# STX3.net
KiCad netlist of a schematic drawn in EAGLE
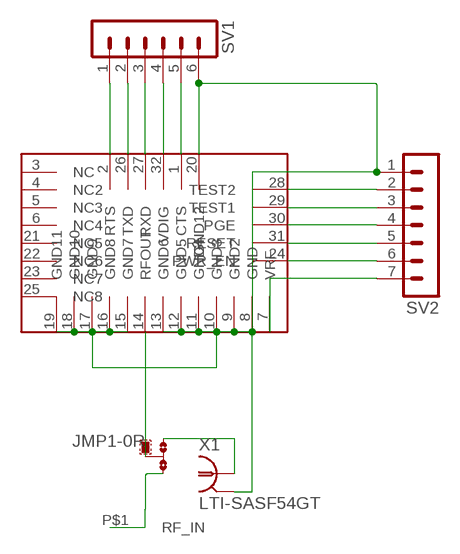
[diagram p0: schematic, sheet 1]

(export (version "E")
  (design (tool "Eeschema 10.0.6"))
  (components
    (comp (ref "JMP1")
      (value "0R-JUMPC")
      (footprint "eagle-import:C0R-JMP")
      (libsource (lib "eagle-import") (part "0R-JUMPC"))
    )
    (comp (ref "SV1")
      (value "MA06-1")
      (footprint "eagle-import:MA06-1")
      (libsource (lib "eagle-import") (part "MA06-1"))
    )
    (comp (ref "SV2")
      (value "MA07-1")
      (footprint "eagle-import:MA07-1")
      (libsource (lib "eagle-import") (part "MA07-1"))
    )
    (comp (ref "U$1")
      (value "STX3")
      (footprint "eagle-import:STX3")
      (libsource (lib "eagle-import") (part "STX3"))
    )
    (comp (ref "U$2")
      (value "GSANTENNA")
      (footprint "eagle-import:GSANTENNA")
      (libsource (lib "eagle-import") (part "GSANTENNA"))
    )
    (comp (ref "X1")
      (value "LTI-SASF54GT")
      (footprint "eagle-import:LTI-SASF54GT")
      (libsource (lib "eagle-import") (part "LTI-SASF54GT"))
    )
  )
  (nets
    (net (code "1") (name "Net-(JMP1-Pad1)") (class "Default")
      (node (ref "JMP1") (pin "1") (pinfunction "1_1") (pintype "passive"))
      (node (ref "X1") (pin "1") (pinfunction "1_1") (pintype "passive"))
    )
    (net (code "2") (name "Net-(U$1-CTS)") (class "Default")
      (node (ref "SV1") (pin "5") (pinfunction "5_5") (pintype "passive"))
      (node (ref "U$1") (pin "1") (pinfunction "CTS_1") (pintype "bidirectional"))
    )
    (net (code "3") (name "Net-(U$1-GND)") (class "Default")
      (node (ref "SV1") (pin "6") (pinfunction "6_6") (pintype "passive"))
      (node (ref "SV2") (pin "1") (pinfunction "1_1") (pintype "passive"))
      (node (ref "U$1") (pin "10") (pinfunction "GND3_10") (pintype "bidirectional"))
      (node (ref "U$1") (pin "11") (pinfunction "GND4_11") (pintype "bidirectional"))
      (node (ref "U$1") (pin "12") (pinfunction "GND5_12") (pintype "bidirectional"))
      (node (ref "U$1") (pin "13") (pinfunction "GND6_13") (pintype "bidirectional"))
      (node (ref "U$1") (pin "15") (pinfunction "GND7_15") (pintype "bidirectional"))
      (node (ref "U$1") (pin "16") (pinfunction "GND8_16") (pintype "bidirectional"))
      (node (ref "U$1") (pin "17") (pinfunction "GND9_17") (pintype "bidirectional"))
      (node (ref "U$1") (pin "18") (pinfunction "GND10_18") (pintype "bidirectional"))
      (node (ref "U$1") (pin "19") (pinfunction "GND11_19") (pintype "bidirectional"))
      (node (ref "U$1") (pin "20") (pinfunction "GND12_20") (pintype "bidirectional"))
      (node (ref "U$1") (pin "8") (pinfunction "GND_8") (pintype "bidirectional"))
      (node (ref "U$1") (pin "9") (pinfunction "GND2_9") (pintype "bidirectional"))
      (node (ref "X1") (pin "2") (pinfunction "2_2") (pintype "passive"))
      (node (ref "X1") (pin "3") (pinfunction "2_3") (pintype "passive"))
      (node (ref "X1") (pin "4") (pinfunction "2_4") (pintype "passive"))
      (node (ref "X1") (pin "5") (pinfunction "2_5") (pintype "passive"))
    )
    (net (code "4") (name "Net-(U$1-PGE)") (class "Default")
      (node (ref "SV2") (pin "4") (pinfunction "4_4") (pintype "passive"))
      (node (ref "U$1") (pin "30") (pinfunction "PGE_30") (pintype "bidirectional"))
    )
    (net (code "5") (name "Net-(U$1-PWR_EN)") (class "Default")
      (node (ref "SV2") (pin "6") (pinfunction "6_6") (pintype "passive"))
      (node (ref "U$1") (pin "24") (pinfunction "PWR_EN_24") (pintype "bidirectional"))
    )
    (net (code "6") (name "Net-(U$1-RESET)") (class "Default")
      (node (ref "SV2") (pin "5") (pinfunction "5_5") (pintype "passive"))
      (node (ref "U$1") (pin "31") (pinfunction "RESET_31") (pintype "bidirectional"))
    )
    (net (code "7") (name "Net-(U$1-RFOUT)") (class "Default")
      (node (ref "JMP1") (pin "2") (pinfunction "2_2") (pintype "passive"))
      (node (ref "U$1") (pin "14") (pinfunction "RFOUT_14") (pintype "bidirectional"))
    )
    (net (code "8") (name "Net-(U$1-RTS)") (class "Default")
      (node (ref "SV1") (pin "1") (pinfunction "1_1") (pintype "passive"))
      (node (ref "U$1") (pin "2") (pinfunction "RTS_2") (pintype "bidirectional"))
    )
    (net (code "9") (name "Net-(U$1-RXD)") (class "Default")
      (node (ref "SV1") (pin "3") (pinfunction "3_3") (pintype "passive"))
      (node (ref "U$1") (pin "27") (pinfunction "RXD_27") (pintype "bidirectional"))
    )
    (net (code "10") (name "Net-(U$1-TEST1)") (class "Default")
      (node (ref "SV2") (pin "3") (pinfunction "3_3") (pintype "passive"))
      (node (ref "U$1") (pin "29") (pinfunction "TEST1_29") (pintype "bidirectional"))
    )
    (net (code "11") (name "Net-(U$1-TEST2)") (class "Default")
      (node (ref "SV2") (pin "2") (pinfunction "2_2") (pintype "passive"))
      (node (ref "U$1") (pin "28") (pinfunction "TEST2_28") (pintype "bidirectional"))
    )
    (net (code "12") (name "Net-(U$1-TXD)") (class "Default")
      (node (ref "SV1") (pin "2") (pinfunction "2_2") (pintype "passive"))
      (node (ref "U$1") (pin "26") (pinfunction "TXD_26") (pintype "bidirectional"))
    )
    (net (code "13") (name "Net-(U$1-VDIG)") (class "Default")
      (node (ref "SV1") (pin "4") (pinfunction "4_4") (pintype "passive"))
      (node (ref "U$1") (pin "32") (pinfunction "VDIG_32") (pintype "bidirectional"))
    )
    (net (code "14") (name "Net-(U$1-VRF)") (class "Default")
      (node (ref "SV2") (pin "7") (pinfunction "7_7") (pintype "passive"))
      (node (ref "U$1") (pin "7") (pinfunction "VRF_7") (pintype "bidirectional"))
    )
    (net (code "15") (name "Net-(U$2-RF_IN)") (class "Default")
      (node (ref "JMP1") (pin "3") (pinfunction "3_3") (pintype "passive"))
      (node (ref "U$2") (pin "P$1") (pinfunction "RF_IN_P$1") (pintype "bidirectional"))
    )
    (net (code "16") (name "unconnected-(U$1-NC-Pad3)") (class "Default")
      (node (ref "U$1") (pin "3") (pinfunction "NC_3") (pintype "bidirectional"))
    )
    (net (code "17") (name "unconnected-(U$1-NC2-Pad4)") (class "Default")
      (node (ref "U$1") (pin "4") (pinfunction "NC2_4") (pintype "bidirectional"))
    )
    (net (code "18") (name "unconnected-(U$1-NC3-Pad5)") (class "Default")
      (node (ref "U$1") (pin "5") (pinfunction "NC3_5") (pintype "bidirectional"))
    )
    (net (code "19") (name "unconnected-(U$1-NC4-Pad6)") (class "Default")
      (node (ref "U$1") (pin "6") (pinfunction "NC4_6") (pintype "bidirectional"))
    )
    (net (code "20") (name "unconnected-(U$1-NC5-Pad21)") (class "Default")
      (node (ref "U$1") (pin "21") (pinfunction "NC5_21") (pintype "bidirectional"))
    )
    (net (code "21") (name "unconnected-(U$1-NC6-Pad22)") (class "Default")
      (node (ref "U$1") (pin "22") (pinfunction "NC6_22") (pintype "bidirectional"))
    )
    (net (code "22") (name "unconnected-(U$1-NC7-Pad23)") (class "Default")
      (node (ref "U$1") (pin "23") (pinfunction "NC7_23") (pintype "bidirectional"))
    )
    (net (code "23") (name "unconnected-(U$1-NC8-Pad25)") (class "Default")
      (node (ref "U$1") (pin "25") (pinfunction "NC8_25") (pintype "bidirectional"))
    )
  )
)
